# Shield.net
KiCad netlist of a schematic drawn in Altium Designer
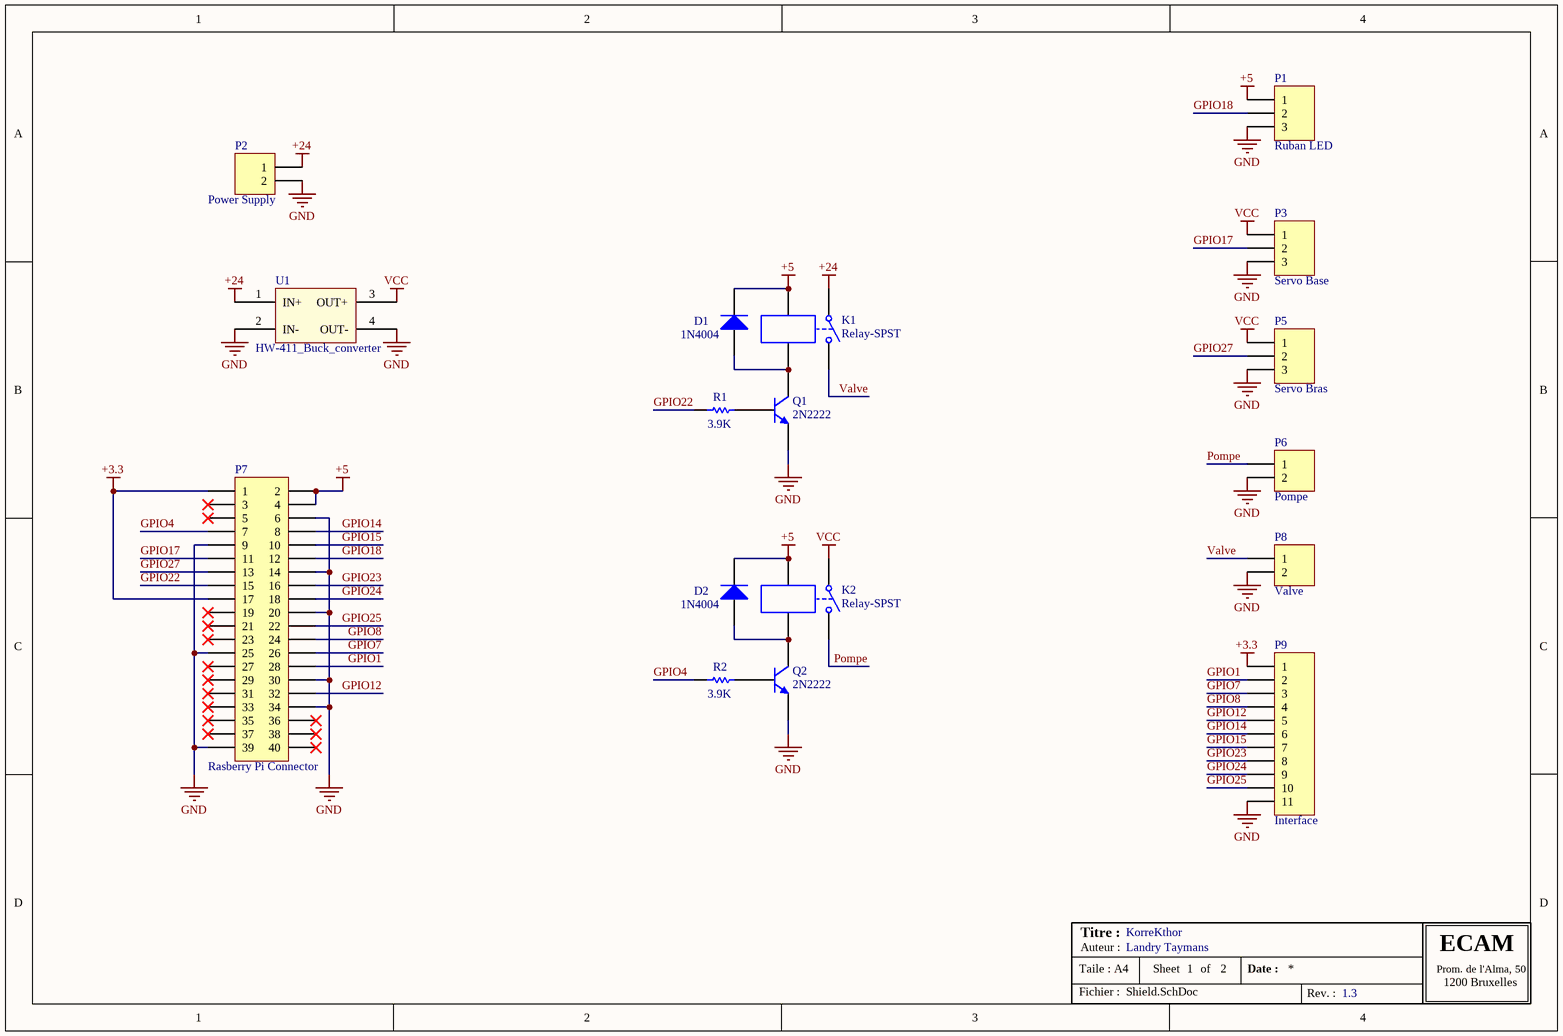
[diagram p0: Shield.SchDoc]

(export (version "E")
  (design (tool "Eeschema 10.0.6"))
  (components
    (comp (ref "D1")
      (value "1N4004")
      (footprint "DO-41")
      (description "1 Amp General Purpose Rectifier")
      (fields (field (name "PUBLISHER") "Altium Limited"))
      (libsource (lib "Miscellaneous Devices") (part "Diode 1N4004"))
    )
    (comp (ref "D2")
      (value "1N4004")
      (footprint "DO-41")
      (description "1 Amp General Purpose Rectifier")
      (fields (field (name "PUBLISHER") "Altium Limited"))
      (libsource (lib "Miscellaneous Devices") (part "Diode 1N4004"))
    )
    (comp (ref "K1")
      (value "Relay-SPST")
      (footprint "RELAY_OJE-SH_series")
      (description "Single-Pole Single-Throw Relay")
      (fields (field (name "PUBLISHER") "Altium Limited"))
      (libsource (lib "Schlib1") (part "Relay-SPST"))
    )
    (comp (ref "K2")
      (value "Relay-SPST")
      (footprint "RELAY_OJE-SH_series")
      (description "Single-Pole Single-Throw Relay")
      (fields (field (name "PUBLISHER") "Altium Limited"))
      (libsource (lib "Schlib1") (part "Relay-SPST"))
    )
    (comp (ref "P1")
      (value "Ruban LED")
      (footprint "Conn_1X3")
      (description "Header, 3-Pin")
      (fields (field (name "PUBLISHER") "Altium Limited"))
      (libsource (lib "Schlib1") (part "Header 3"))
    )
    (comp (ref "P2")
      (value "Power Supply")
      (footprint "Bornier_1X2")
      (description "Header, 2-Pin")
      (fields (field (name "PUBLISHER") "Altium Limited"))
      (libsource (lib "") (part "Header 2_1"))
    )
    (comp (ref "P3")
      (value "Servo Base")
      (footprint "Conn_1X3")
      (description "Header, 3-Pin")
      (fields (field (name "PUBLISHER") "Altium Limited"))
      (libsource (lib "Schlib1") (part "Header 3"))
    )
    (comp (ref "P5")
      (value "Servo Bras")
      (footprint "Conn_1X3")
      (description "Header, 3-Pin")
      (fields (field (name "PUBLISHER") "Altium Limited"))
      (libsource (lib "Schlib1") (part "Header 3"))
    )
    (comp (ref "P6")
      (value "Pompe")
      (footprint "Bornier_1X2")
      (description "Header, 2-Pin")
      (fields (field (name "PUBLISHER") "Altium Limited"))
      (libsource (lib "Schlib1") (part "Header 2"))
    )
    (comp (ref "P7")
      (value "Rasberry Pi Connector")
      (footprint "HDR2X20")
      (description "Header, 20-Pin, Dual row")
      (fields (field (name "PUBLISHER") "Altium Limited"))
      (libsource (lib "Schlib1") (part "MHDR2X20"))
    )
    (comp (ref "P8")
      (value "Valve")
      (footprint "Bornier_1X2")
      (description "Header, 2-Pin")
      (fields (field (name "PUBLISHER") "Altium Limited"))
      (libsource (lib "Schlib1") (part "Header 2"))
    )
    (comp (ref "P9")
      (value "Interface")
      (footprint "Conn_1X11")
      (description "Header, 11-Pin")
      (fields (field (name "PUBLISHER") "Altium Limited"))
      (libsource (lib "Schlib1") (part "Header 11"))
    )
    (comp (ref "Q1")
      (value "2N2222")
      (footprint "TO-92")
      (description "NPN Bipolar Transistor")
      (fields (field (name "PUBLISHER") "Altium Limited"))
      (libsource (lib "Schlib1") (part "NPN"))
    )
    (comp (ref "Q2")
      (value "2N2222")
      (footprint "TO-92")
      (description "NPN Bipolar Transistor")
      (fields (field (name "PUBLISHER") "Altium Limited"))
      (libsource (lib "Schlib1") (part "NPN"))
    )
    (comp (ref "R1")
      (value "3.9K")
      (footprint "AXIAL-0.3")
      (description "Resistor")
      (fields (field (name "Comment") "Res1") (field (name "PUBLISHER") "Altium Limited"))
      (libsource (lib "Miscellaneous Devices") (part "Res1"))
    )
    (comp (ref "R2")
      (value "3.9K")
      (footprint "AXIAL-0.3")
      (description "Resistor")
      (fields (field (name "Comment") "Res1") (field (name "PUBLISHER") "Altium Limited"))
      (libsource (lib "Miscellaneous Devices") (part "Res1"))
    )
    (comp (ref "U1")
      (value "HW-411_Buck_converter")
      (footprint "HW-411_Buck_converter")
      (description "Buck converter board")
      (libsource (lib "Schlib1") (part "HW-411_Buck_converter"))
    )
  )
  (nets
    (net (code "1") (name "+3.3") (class "Default")
      (node (ref "P7") (pin "1") (pinfunction "1_1") (pintype "passive"))
      (node (ref "P7") (pin "17") (pinfunction "17_17") (pintype "passive"))
      (node (ref "P9") (pin "1") (pinfunction "1_1") (pintype "passive"))
    )
    (net (code "2") (name "+5") (class "Default")
      (node (ref "D1") (pin "2") (pinfunction "K_2") (pintype "passive"))
      (node (ref "D2") (pin "2") (pinfunction "K_2") (pintype "passive"))
      (node (ref "K1") (pin "3") (pinfunction "3_3") (pintype "passive"))
      (node (ref "K2") (pin "3") (pinfunction "3_3") (pintype "passive"))
      (node (ref "P1") (pin "1") (pinfunction "1_1") (pintype "passive"))
      (node (ref "P7") (pin "2") (pinfunction "2_2") (pintype "passive"))
      (node (ref "P7") (pin "4") (pinfunction "4_4") (pintype "passive"))
    )
    (net (code "3") (name "+24") (class "Default")
      (node (ref "K1") (pin "1") (pinfunction "1_1") (pintype "passive"))
      (node (ref "P2") (pin "1") (pinfunction "1_1") (pintype "passive"))
      (node (ref "U1") (pin "1") (pinfunction "IN+_1") (pintype "power_in"))
    )
    (net (code "4") (name "/GPIO1") (class "Default")
      (node (ref "P7") (pin "28") (pinfunction "28_28") (pintype "passive"))
      (node (ref "P9") (pin "2") (pinfunction "2_2") (pintype "passive"))
    )
    (net (code "5") (name "/GPIO4") (class "Default")
      (node (ref "P7") (pin "7") (pinfunction "7_7") (pintype "passive"))
      (node (ref "R2") (pin "1") (pinfunction "1_1") (pintype "passive"))
    )
    (net (code "6") (name "/GPIO7") (class "Default")
      (node (ref "P7") (pin "26") (pinfunction "26_26") (pintype "passive"))
      (node (ref "P9") (pin "3") (pinfunction "3_3") (pintype "passive"))
    )
    (net (code "7") (name "/GPIO8") (class "Default")
      (node (ref "P7") (pin "24") (pinfunction "24_24") (pintype "passive"))
      (node (ref "P9") (pin "4") (pinfunction "4_4") (pintype "passive"))
    )
    (net (code "8") (name "/GPIO12") (class "Default")
      (node (ref "P7") (pin "32") (pinfunction "32_32") (pintype "passive"))
      (node (ref "P9") (pin "5") (pinfunction "5_5") (pintype "passive"))
    )
    (net (code "9") (name "/GPIO14") (class "Default")
      (node (ref "P7") (pin "8") (pinfunction "8_8") (pintype "passive"))
      (node (ref "P9") (pin "6") (pinfunction "6_6") (pintype "passive"))
    )
    (net (code "10") (name "/GPIO15") (class "Default")
      (node (ref "P7") (pin "10") (pinfunction "10_10") (pintype "passive"))
      (node (ref "P9") (pin "7") (pinfunction "7_7") (pintype "passive"))
    )
    (net (code "11") (name "/GPIO17") (class "Default")
      (node (ref "P3") (pin "2") (pinfunction "2_2") (pintype "passive"))
      (node (ref "P7") (pin "11") (pinfunction "11_11") (pintype "passive"))
    )
    (net (code "12") (name "/GPIO18") (class "Default")
      (node (ref "P1") (pin "2") (pinfunction "2_2") (pintype "passive"))
      (node (ref "P7") (pin "12") (pinfunction "12_12") (pintype "passive"))
    )
    (net (code "13") (name "/GPIO22") (class "Default")
      (node (ref "P7") (pin "15") (pinfunction "15_15") (pintype "passive"))
      (node (ref "R1") (pin "1") (pinfunction "1_1") (pintype "passive"))
    )
    (net (code "14") (name "/GPIO23") (class "Default")
      (node (ref "P7") (pin "16") (pinfunction "16_16") (pintype "passive"))
      (node (ref "P9") (pin "8") (pinfunction "8_8") (pintype "passive"))
    )
    (net (code "15") (name "/GPIO24") (class "Default")
      (node (ref "P7") (pin "18") (pinfunction "18_18") (pintype "passive"))
      (node (ref "P9") (pin "9") (pinfunction "9_9") (pintype "passive"))
    )
    (net (code "16") (name "/GPIO25") (class "Default")
      (node (ref "P7") (pin "22") (pinfunction "22_22") (pintype "passive"))
      (node (ref "P9") (pin "10") (pinfunction "10_10") (pintype "passive"))
    )
    (net (code "17") (name "/GPIO27") (class "Default")
      (node (ref "P5") (pin "2") (pinfunction "2_2") (pintype "passive"))
      (node (ref "P7") (pin "13") (pinfunction "13_13") (pintype "passive"))
    )
    (net (code "18") (name "/Pompe") (class "Default")
      (node (ref "K2") (pin "2") (pinfunction "2_2") (pintype "passive"))
      (node (ref "P6") (pin "1") (pinfunction "1_1") (pintype "passive"))
    )
    (net (code "19") (name "/Valve") (class "Default")
      (node (ref "K1") (pin "2") (pinfunction "2_2") (pintype "passive"))
      (node (ref "P8") (pin "1") (pinfunction "1_1") (pintype "passive"))
    )
    (net (code "20") (name "GND") (class "Default")
      (node (ref "P1") (pin "3") (pinfunction "3_3") (pintype "passive"))
      (node (ref "P2") (pin "2") (pinfunction "2_2") (pintype "passive"))
      (node (ref "P3") (pin "3") (pinfunction "3_3") (pintype "passive"))
      (node (ref "P5") (pin "3") (pinfunction "3_3") (pintype "passive"))
      (node (ref "P6") (pin "2") (pinfunction "2_2") (pintype "passive"))
      (node (ref "P7") (pin "14") (pinfunction "14_14") (pintype "passive"))
      (node (ref "P7") (pin "20") (pinfunction "20_20") (pintype "passive"))
      (node (ref "P7") (pin "25") (pinfunction "25_25") (pintype "passive"))
      (node (ref "P7") (pin "30") (pinfunction "30_30") (pintype "passive"))
      (node (ref "P7") (pin "34") (pinfunction "34_34") (pintype "passive"))
      (node (ref "P7") (pin "39") (pinfunction "39_39") (pintype "passive"))
      (node (ref "P7") (pin "6") (pinfunction "6_6") (pintype "passive"))
      (node (ref "P7") (pin "9") (pinfunction "9_9") (pintype "passive"))
      (node (ref "P8") (pin "2") (pinfunction "2_2") (pintype "passive"))
      (node (ref "P9") (pin "11") (pinfunction "11_11") (pintype "passive"))
      (node (ref "Q1") (pin "3") (pinfunction "E_3") (pintype "passive"))
      (node (ref "Q2") (pin "3") (pinfunction "E_3") (pintype "passive"))
      (node (ref "U1") (pin "2") (pinfunction "IN-_2") (pintype "power_in"))
      (node (ref "U1") (pin "4") (pinfunction "OUT-_4") (pintype "power_in"))
    )
    (net (code "21") (name "Net-(D1-A)") (class "Default")
      (node (ref "D1") (pin "1") (pinfunction "A_1") (pintype "passive"))
      (node (ref "K1") (pin "4") (pinfunction "4_4") (pintype "passive"))
      (node (ref "Q1") (pin "1") (pinfunction "C_1") (pintype "passive"))
    )
    (net (code "22") (name "Net-(D2-A)") (class "Default")
      (node (ref "D2") (pin "1") (pinfunction "A_1") (pintype "passive"))
      (node (ref "K2") (pin "4") (pinfunction "4_4") (pintype "passive"))
      (node (ref "Q2") (pin "1") (pinfunction "C_1") (pintype "passive"))
    )
    (net (code "23") (name "Net-(Q1-B)") (class "Default")
      (node (ref "Q1") (pin "2") (pinfunction "B_2") (pintype "passive"))
      (node (ref "R1") (pin "2") (pinfunction "2_2") (pintype "passive"))
    )
    (net (code "24") (name "Net-(Q2-B)") (class "Default")
      (node (ref "Q2") (pin "2") (pinfunction "B_2") (pintype "passive"))
      (node (ref "R2") (pin "2") (pinfunction "2_2") (pintype "passive"))
    )
    (net (code "25") (name "VCC") (class "Default")
      (node (ref "K2") (pin "1") (pinfunction "1_1") (pintype "passive"))
      (node (ref "P3") (pin "1") (pinfunction "1_1") (pintype "passive"))
      (node (ref "P5") (pin "1") (pinfunction "1_1") (pintype "passive"))
      (node (ref "U1") (pin "3") (pinfunction "OUT+_3") (pintype "power_in"))
    )
    (net (code "26") (name "unconnected-(P7-Pad3)") (class "Default")
      (node (ref "P7") (pin "3") (pinfunction "3_3") (pintype "passive+no_connect"))
    )
    (net (code "27") (name "unconnected-(P7-Pad5)") (class "Default")
      (node (ref "P7") (pin "5") (pinfunction "5_5") (pintype "passive+no_connect"))
    )
    (net (code "28") (name "unconnected-(P7-Pad19)") (class "Default")
      (node (ref "P7") (pin "19") (pinfunction "19_19") (pintype "passive+no_connect"))
    )
    (net (code "29") (name "unconnected-(P7-Pad21)") (class "Default")
      (node (ref "P7") (pin "21") (pinfunction "21_21") (pintype "passive+no_connect"))
    )
    (net (code "30") (name "unconnected-(P7-Pad23)") (class "Default")
      (node (ref "P7") (pin "23") (pinfunction "23_23") (pintype "passive+no_connect"))
    )
    (net (code "31") (name "unconnected-(P7-Pad27)") (class "Default")
      (node (ref "P7") (pin "27") (pinfunction "27_27") (pintype "passive+no_connect"))
    )
    (net (code "32") (name "unconnected-(P7-Pad29)") (class "Default")
      (node (ref "P7") (pin "29") (pinfunction "29_29") (pintype "passive+no_connect"))
    )
    (net (code "33") (name "unconnected-(P7-Pad31)") (class "Default")
      (node (ref "P7") (pin "31") (pinfunction "31_31") (pintype "passive+no_connect"))
    )
    (net (code "34") (name "unconnected-(P7-Pad33)") (class "Default")
      (node (ref "P7") (pin "33") (pinfunction "33_33") (pintype "passive+no_connect"))
    )
    (net (code "35") (name "unconnected-(P7-Pad35)") (class "Default")
      (node (ref "P7") (pin "35") (pinfunction "35_35") (pintype "passive+no_connect"))
    )
    (net (code "36") (name "unconnected-(P7-Pad36)") (class "Default")
      (node (ref "P7") (pin "36") (pinfunction "36_36") (pintype "passive+no_connect"))
    )
    (net (code "37") (name "unconnected-(P7-Pad37)") (class "Default")
      (node (ref "P7") (pin "37") (pinfunction "37_37") (pintype "passive+no_connect"))
    )
    (net (code "38") (name "unconnected-(P7-Pad38)") (class "Default")
      (node (ref "P7") (pin "38") (pinfunction "38_38") (pintype "passive+no_connect"))
    )
    (net (code "39") (name "unconnected-(P7-Pad40)") (class "Default")
      (node (ref "P7") (pin "40") (pinfunction "40_40") (pintype "passive+no_connect"))
    )
  )
)
